# USB.net
KiCad netlist of a schematic drawn in Altium Designer
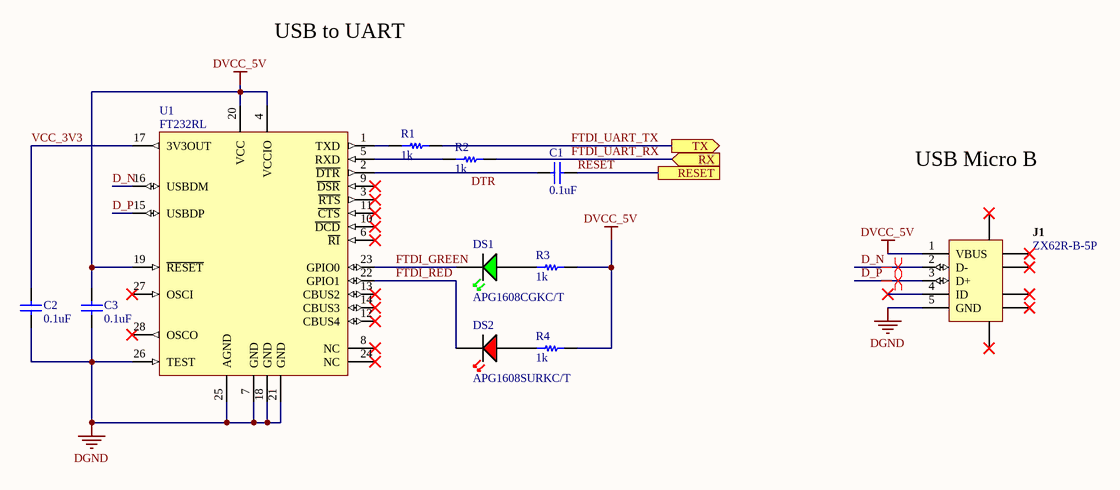
[diagram p0: USB.SchDoc]

(export (version "E")
  (design (tool "Eeschema 10.0.6"))
  (components
    (comp (ref "C1")
      (value "0.1uF")
      (footprint "CAP SMT 0603")
      (libsource (lib "Components") (part "Capacitor 0.1uF 25V 0603"))
    )
    (comp (ref "C2")
      (value "0.1uF")
      (footprint "CAP SMT 0603")
      (libsource (lib "Components") (part "Capacitor 0.1uF 25V 0603"))
    )
    (comp (ref "C3")
      (value "0.1uF")
      (footprint "CAP SMT 0603")
      (libsource (lib "Components") (part "Capacitor 0.1uF 25V 0603"))
    )
    (comp (ref "DS1")
      (value "APG1608CGKC/T")
      (footprint "GREEN LED")
      (libsource (lib "CPRacingUnifiedLibrary") (part "Green LED"))
    )
    (comp (ref "DS2")
      (value "APG1608SURKC/T")
      (footprint "RED LED")
      (libsource (lib "CPRacingUnifiedLibrary") (part "RED LED"))
    )
    (comp (ref "J1")
      (value "ZX62R-B-5P")
      (footprint "HIRO-ZX62R-B-5P_V")
      (description "Connector; USBMicro-B,Reverse type, SMT; 5 Position; Right Angle")
      (libsource (lib "Altium Content Vault") (part "HIRO-ZX62R-B-5P-5"))
    )
    (comp (ref "R1")
      (value "1k")
      (footprint "RES SMT 0805")
      (libsource (lib "Components") (part "Resistor 1k 1% 0805"))
    )
    (comp (ref "R2")
      (value "1k")
      (footprint "RES SMT 0805")
      (libsource (lib "Components") (part "Resistor 1k 1% 0805"))
    )
    (comp (ref "R3")
      (value "1k")
      (footprint "RES SMT 0805")
      (libsource (lib "Components") (part "Resistor 1k 1% 0805"))
    )
    (comp (ref "R4")
      (value "1k")
      (footprint "RES SMT 0805")
      (libsource (lib "Components") (part "Resistor 1k 1% 0805"))
    )
    (comp (ref "U1")
      (value "FT232RL")
      (footprint "SSOP-28_L")
      (description "USB UART Asynchronous Serial Data Transfer Chip, SSOP-28, Tape and Reel")
      (libsource (lib "Altium Content Vault") (part "COM-UART-FT232R-IL28"))
    )
  )
  (nets
    (net (code "1") (name "/DTR") (class "Default")
      (node (ref "C1") (pin "1") (pinfunction "1_1") (pintype "passive"))
      (node (ref "U1") (pin "2") (pinfunction "~{DTR}_2") (pintype "output"))
    )
    (net (code "2") (name "/D_N") (class "Default")
      (node (ref "J1") (pin "2") (pinfunction "D-_2") (pintype "bidirectional"))
      (node (ref "U1") (pin "16") (pinfunction "USBDM_16") (pintype "bidirectional"))
    )
    (net (code "3") (name "/D_P") (class "Default")
      (node (ref "J1") (pin "3") (pinfunction "D+_3") (pintype "bidirectional"))
      (node (ref "U1") (pin "15") (pinfunction "USBDP_15") (pintype "bidirectional"))
    )
    (net (code "4") (name "/FTDI_GREEN") (class "Default")
      (node (ref "DS1") (pin "1") (pinfunction "1_1") (pintype "passive"))
      (node (ref "U1") (pin "23") (pinfunction "GPIO0_23") (pintype "bidirectional"))
    )
    (net (code "5") (name "/FTDI_RED") (class "Default")
      (node (ref "DS2") (pin "1") (pinfunction "1_1") (pintype "passive"))
      (node (ref "U1") (pin "22") (pinfunction "GPIO1_22") (pintype "bidirectional"))
    )
    (net (code "6") (name "/FTDI_UART_RX") (class "Default")
      (node (ref "R2") (pin "2") (pinfunction "2_2") (pintype "passive"))
    )
    (net (code "7") (name "/FTDI_UART_TX") (class "Default")
      (node (ref "R1") (pin "2") (pinfunction "2_2") (pintype "passive"))
    )
    (net (code "8") (name "/RESET") (class "Default")
      (node (ref "C1") (pin "2") (pinfunction "2_2") (pintype "passive"))
    )
    (net (code "9") (name "/VCC_3V3") (class "Default")
      (node (ref "C2") (pin "2") (pinfunction "2_2") (pintype "passive"))
      (node (ref "U1") (pin "17") (pinfunction "3V3OUT_17") (pintype "output"))
    )
    (net (code "10") (name "DGND") (class "Default")
      (node (ref "C2") (pin "1") (pinfunction "1_1") (pintype "passive"))
      (node (ref "C3") (pin "1") (pinfunction "1_1") (pintype "passive"))
      (node (ref "J1") (pin "5") (pinfunction "GND_5") (pintype "power_in"))
      (node (ref "U1") (pin "18") (pinfunction "GND_18") (pintype "power_in"))
      (node (ref "U1") (pin "21") (pinfunction "GND_21") (pintype "power_in"))
      (node (ref "U1") (pin "25") (pinfunction "AGND_25") (pintype "power_in"))
      (node (ref "U1") (pin "26") (pinfunction "TEST_26") (pintype "input"))
      (node (ref "U1") (pin "7") (pinfunction "GND_7") (pintype "power_in"))
    )
    (net (code "11") (name "DVCC_5V") (class "Default")
      (node (ref "C3") (pin "2") (pinfunction "2_2") (pintype "passive"))
      (node (ref "J1") (pin "1") (pinfunction "VBUS_1") (pintype "power_in"))
      (node (ref "R3") (pin "2") (pinfunction "2_2") (pintype "passive"))
      (node (ref "R4") (pin "2") (pinfunction "2_2") (pintype "passive"))
      (node (ref "U1") (pin "19") (pinfunction "~{RESET}_19") (pintype "input"))
      (node (ref "U1") (pin "20") (pinfunction "VCC_20") (pintype "power_in"))
      (node (ref "U1") (pin "4") (pinfunction "VCCIO_4") (pintype "power_in"))
    )
    (net (code "12") (name "Net-(DS1-Pad2)") (class "Default")
      (node (ref "DS1") (pin "2") (pinfunction "2_2") (pintype "passive"))
      (node (ref "R3") (pin "1") (pinfunction "1_1") (pintype "passive"))
    )
    (net (code "13") (name "Net-(DS2-Pad2)") (class "Default")
      (node (ref "DS2") (pin "2") (pinfunction "2_2") (pintype "passive"))
      (node (ref "R4") (pin "1") (pinfunction "1_1") (pintype "passive"))
    )
    (net (code "14") (name "Net-(U1-RXD)") (class "Default")
      (node (ref "R2") (pin "1") (pinfunction "1_1") (pintype "passive"))
      (node (ref "U1") (pin "5") (pinfunction "RXD_5") (pintype "input"))
    )
    (net (code "15") (name "Net-(U1-TXD)") (class "Default")
      (node (ref "R1") (pin "1") (pinfunction "1_1") (pintype "passive"))
      (node (ref "U1") (pin "1") (pinfunction "TXD_1") (pintype "output"))
    )
    (net (code "16") (name "unconnected-(J1-ID-Pad4)") (class "Default")
      (node (ref "J1") (pin "4") (pinfunction "ID_4") (pintype "passive+no_connect"))
    )
    (net (code "17") (name "unconnected-(J1-SHLD-Pad6)") (class "Default")
      (node (ref "J1") (pin "6") (pinfunction "SHLD_6") (pintype "passive+no_connect"))
    )
    (net (code "18") (name "unconnected-(J1-SHLD-Pad7)") (class "Default")
      (node (ref "J1") (pin "7") (pinfunction "SHLD_7") (pintype "passive+no_connect"))
    )
    (net (code "19") (name "unconnected-(J1-SHLD-Pad8)") (class "Default")
      (node (ref "J1") (pin "8") (pinfunction "SHLD_8") (pintype "passive+no_connect"))
    )
    (net (code "20") (name "unconnected-(J1-SHLD-Pad9)") (class "Default")
      (node (ref "J1") (pin "9") (pinfunction "SHLD_9") (pintype "passive+no_connect"))
    )
    (net (code "21") (name "unconnected-(J1-SHLD-Pad10)") (class "Default")
      (node (ref "J1") (pin "10") (pinfunction "SHLD_10") (pintype "passive+no_connect"))
    )
    (net (code "22") (name "unconnected-(J1-SHLD-Pad11)") (class "Default")
      (node (ref "J1") (pin "11") (pinfunction "SHLD_11") (pintype "passive+no_connect"))
    )
    (net (code "23") (name "unconnected-(U1-CBUS2-Pad13)") (class "Default")
      (node (ref "U1") (pin "13") (pinfunction "CBUS2_13") (pintype "bidirectional+no_connect"))
    )
    (net (code "24") (name "unconnected-(U1-CBUS3-Pad14)") (class "Default")
      (node (ref "U1") (pin "14") (pinfunction "CBUS3_14") (pintype "bidirectional+no_connect"))
    )
    (net (code "25") (name "unconnected-(U1-CBUS4-Pad12)") (class "Default")
      (node (ref "U1") (pin "12") (pinfunction "CBUS4_12") (pintype "bidirectional+no_connect"))
    )
    (net (code "26") (name "unconnected-(U1-NC-Pad8)") (class "Default")
      (node (ref "U1") (pin "8") (pinfunction "NC_8") (pintype "passive+no_connect"))
    )
    (net (code "27") (name "unconnected-(U1-NC-Pad24)") (class "Default")
      (node (ref "U1") (pin "24") (pinfunction "NC_24") (pintype "passive+no_connect"))
    )
    (net (code "28") (name "unconnected-(U1-OSCI-Pad27)") (class "Default")
      (node (ref "U1") (pin "27") (pinfunction "OSCI_27") (pintype "input+no_connect"))
    )
    (net (code "29") (name "unconnected-(U1-OSCO-Pad28)") (class "Default")
      (node (ref "U1") (pin "28") (pinfunction "OSCO_28") (pintype "output+no_connect"))
    )
    (net (code "30") (name "unconnected-(U1-~{CTS}-Pad11)") (class "Default")
      (node (ref "U1") (pin "11") (pinfunction "~{CTS}_11") (pintype "input+no_connect"))
    )
    (net (code "31") (name "unconnected-(U1-~{DCD}-Pad10)") (class "Default")
      (node (ref "U1") (pin "10") (pinfunction "~{DCD}_10") (pintype "input+no_connect"))
    )
    (net (code "32") (name "unconnected-(U1-~{DSR}-Pad9)") (class "Default")
      (node (ref "U1") (pin "9") (pinfunction "~{DSR}_9") (pintype "input+no_connect"))
    )
    (net (code "33") (name "unconnected-(U1-~{RI}-Pad6)") (class "Default")
      (node (ref "U1") (pin "6") (pinfunction "~{RI}_6") (pintype "input+no_connect"))
    )
    (net (code "34") (name "unconnected-(U1-~{RTS}-Pad3)") (class "Default")
      (node (ref "U1") (pin "3") (pinfunction "~{RTS}_3") (pintype "output+no_connect"))
    )
  )
)
